# PR5007.net
KiCad netlist of a schematic drawn in EAGLE
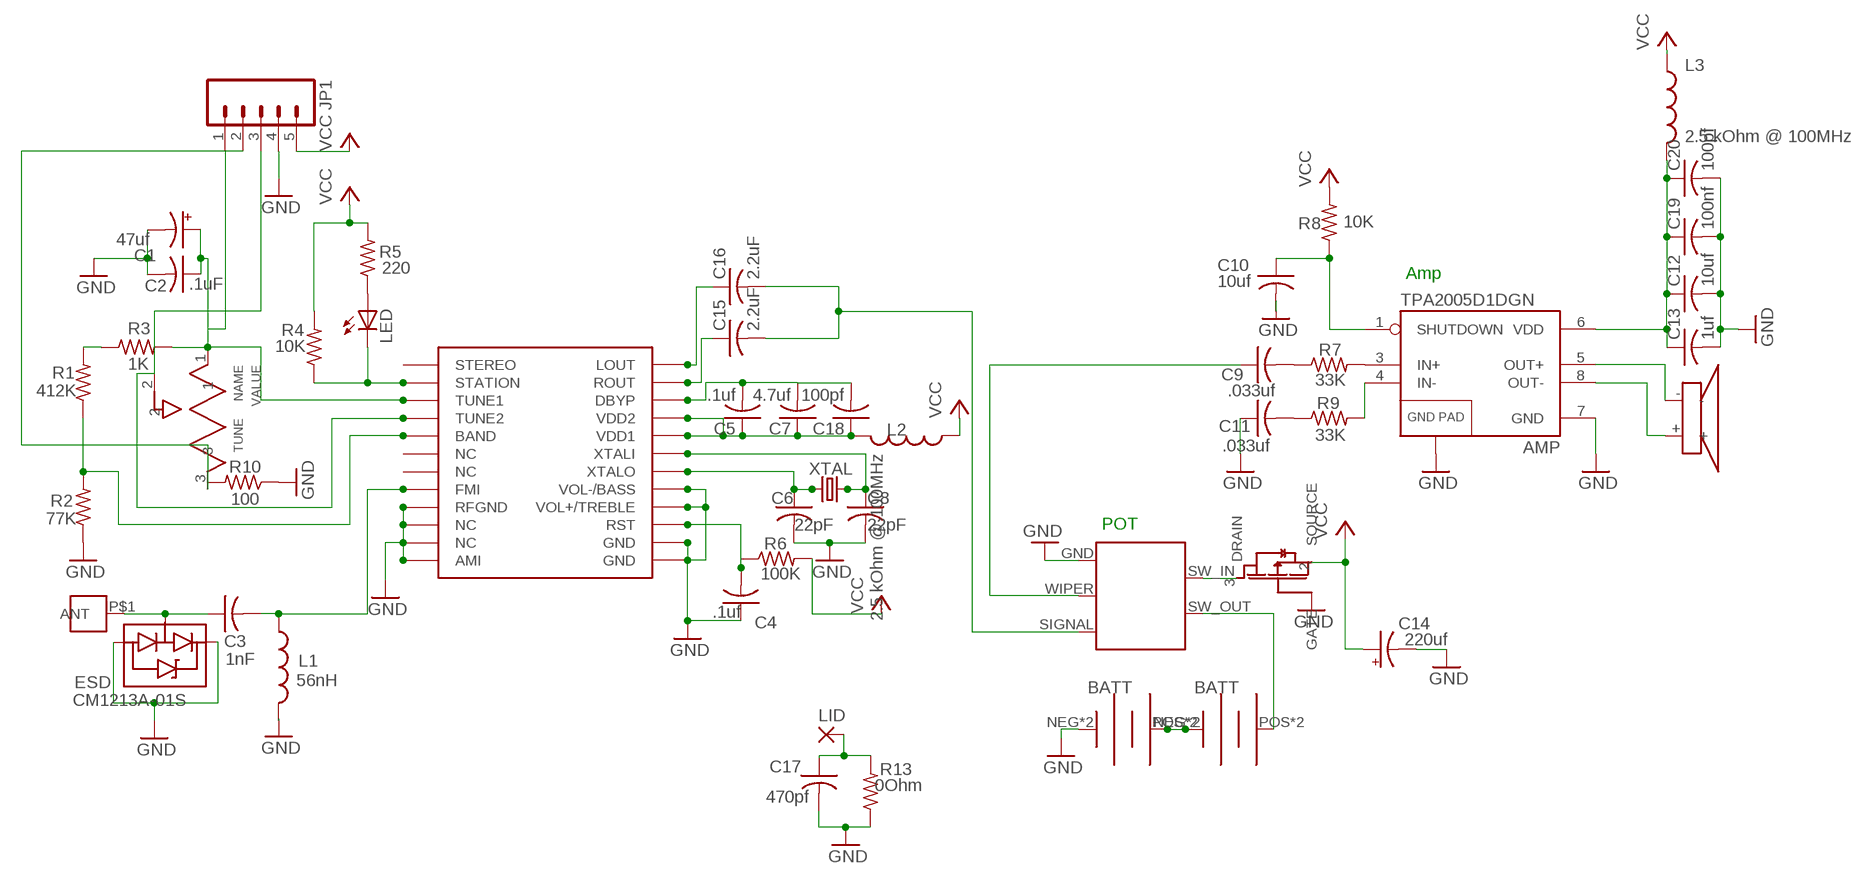
[diagram p0: schematic, sheet 1]

(export (version "E")
  (design (tool "Eeschema 10.0.6"))
  (components
    (comp (ref "AMP")
      (value "TPA2005D1DGN")
      (footprint "eagle-import:POWER-SOP8")
      (libsource (lib "eagle-import") (part "TPA2005D1DGN"))
    )
    (comp (ref "ANT")
      (value "M3_SCREW_POST")
      (footprint "eagle-import:M3_SCREW_POST")
      (libsource (lib "eagle-import") (part "M3_SCREW_POST"))
    )
    (comp (ref "C1")
      (value "47uf")
      (footprint "eagle-import:E2-5")
      (libsource (lib "eagle-import") (part "CPOL-USE2-5"))
    )
    (comp (ref "C2")
      (value ".1uF")
      (footprint "eagle-import:C0603")
      (libsource (lib "eagle-import") (part "C-USC0603"))
    )
    (comp (ref "C3")
      (value "1nF")
      (footprint "eagle-import:C0603")
      (libsource (lib "eagle-import") (part "C-USC0603"))
    )
    (comp (ref "C4")
      (value ".1uf")
      (footprint "eagle-import:C0603")
      (libsource (lib "eagle-import") (part "C-USC0603"))
    )
    (comp (ref "C5")
      (value ".1uf")
      (footprint "eagle-import:C0603")
      (libsource (lib "eagle-import") (part "C-USC0603"))
    )
    (comp (ref "C6")
      (value "22pF")
      (footprint "eagle-import:C0603")
      (libsource (lib "eagle-import") (part "C-USC0603"))
    )
    (comp (ref "C7")
      (value "4.7uf")
      (footprint "eagle-import:C0603")
      (libsource (lib "eagle-import") (part "C-USC0603"))
    )
    (comp (ref "C8")
      (value "22pF")
      (footprint "eagle-import:C0603")
      (libsource (lib "eagle-import") (part "C-USC0603"))
    )
    (comp (ref "C9")
      (value ".033uf")
      (footprint "eagle-import:C0603")
      (libsource (lib "eagle-import") (part "C-USC0603"))
    )
    (comp (ref "C10")
      (value "10uf")
      (footprint "eagle-import:C0603")
      (libsource (lib "eagle-import") (part "C-USC0603"))
    )
    (comp (ref "C11")
      (value ".033uf")
      (footprint "eagle-import:C0603")
      (libsource (lib "eagle-import") (part "C-USC0603"))
    )
    (comp (ref "C12")
      (value "10uf")
      (footprint "eagle-import:C0603")
      (libsource (lib "eagle-import") (part "C-USC0603"))
    )
    (comp (ref "C13")
      (value "1uf")
      (footprint "eagle-import:C0603")
      (libsource (lib "eagle-import") (part "C-USC0603"))
    )
    (comp (ref "C14")
      (value "220uf")
      (footprint "eagle-import:E2-5")
      (libsource (lib "eagle-import") (part "CPOL-USE2-5"))
    )
    (comp (ref "C15")
      (value "2.2uF")
      (footprint "eagle-import:C0603")
      (libsource (lib "eagle-import") (part "C-USC0603"))
    )
    (comp (ref "C16")
      (value "2.2uF")
      (footprint "eagle-import:C0603")
      (libsource (lib "eagle-import") (part "C-USC0603"))
    )
    (comp (ref "C17")
      (value "470pf")
      (footprint "eagle-import:C0805")
      (libsource (lib "eagle-import") (part "C-USC0805"))
    )
    (comp (ref "C18")
      (value "100pf")
      (footprint "eagle-import:C0603")
      (libsource (lib "eagle-import") (part "C-USC0603"))
    )
    (comp (ref "C19")
      (value "100nf")
      (footprint "eagle-import:C0603")
      (libsource (lib "eagle-import") (part "C-USC0603"))
    )
    (comp (ref "C20")
      (value "100pf")
      (footprint "eagle-import:C0603")
      (libsource (lib "eagle-import") (part "C-USC0603"))
    )
    (comp (ref "ESD")
      (value "CM1213A-01S")
      (footprint "eagle-import:SOT23-3")
      (libsource (lib "eagle-import") (part "CM1213A-01S"))
    )
    (comp (ref "FET")
      (value "SI2333DDS")
      (footprint "eagle-import:SI2333DDS")
      (libsource (lib "eagle-import") (part "SI2333DDS"))
    )
    (comp (ref "JP1")
      (value "M05LOCK")
      (footprint "eagle-import:1X05_LOCK")
      (libsource (lib "eagle-import") (part "M05LOCK"))
    )
    (comp (ref "L1")
      (value "56nH")
      (footprint "eagle-import:0603")
      (libsource (lib "eagle-import") (part "INDUCTOR0603"))
    )
    (comp (ref "L2")
      (value "2.5 kOhm @ 100MHz")
      (footprint "eagle-import:0603")
      (libsource (lib "eagle-import") (part "INDUCTOR0603"))
    )
    (comp (ref "L3")
      (value "2.5 kOhm @ 100MHz")
      (footprint "eagle-import:0603")
      (libsource (lib "eagle-import") (part "INDUCTOR0603"))
    )
    (comp (ref "LED")
      (value "LEDCHIPLED_0805")
      (footprint "eagle-import:CHIPLED_0805")
      (libsource (lib "eagle-import") (part "LEDCHIPLED_0805"))
    )
    (comp (ref "LID")
      (value "2,54/1,0")
      (footprint "eagle-import:2,54_1,0")
      (libsource (lib "eagle-import") (part "2,54/1,0"))
    )
    (comp (ref "R1")
      (value "412K")
      (footprint "eagle-import:R0603")
      (libsource (lib "eagle-import") (part "R-US_R0603"))
    )
    (comp (ref "R2")
      (value "77K")
      (footprint "eagle-import:R0603")
      (libsource (lib "eagle-import") (part "R-US_R0603"))
    )
    (comp (ref "R3")
      (value "1K")
      (footprint "eagle-import:R0603")
      (libsource (lib "eagle-import") (part "R-US_R0603"))
    )
    (comp (ref "R4")
      (value "10K")
      (footprint "eagle-import:R0603")
      (libsource (lib "eagle-import") (part "R-US_R0603"))
    )
    (comp (ref "R5")
      (value "220")
      (footprint "eagle-import:R0603")
      (libsource (lib "eagle-import") (part "R-US_R0603"))
    )
    (comp (ref "R6")
      (value "100K")
      (footprint "eagle-import:R0603")
      (libsource (lib "eagle-import") (part "R-US_R0603"))
    )
    (comp (ref "R7")
      (value "33K")
      (footprint "eagle-import:R0603")
      (libsource (lib "eagle-import") (part "R-US_R0603"))
    )
    (comp (ref "R8")
      (value "10K")
      (footprint "eagle-import:R0603")
      (libsource (lib "eagle-import") (part "R-US_R0603"))
    )
    (comp (ref "R9")
      (value "33K")
      (footprint "eagle-import:R0603")
      (libsource (lib "eagle-import") (part "R-US_R0603"))
    )
    (comp (ref "R10")
      (value "100")
      (footprint "eagle-import:R0603")
      (libsource (lib "eagle-import") (part "R-US_R0603"))
    )
    (comp (ref "R13")
      (value "0Ohm")
      (footprint "eagle-import:R0603")
      (libsource (lib "eagle-import") (part "R-US_R0603"))
    )
    (comp (ref "TUNE")
      (value "TUNE")
      (footprint "eagle-import:64XR_BOURNS_TRIMPOT")
      (libsource (lib "eagle-import") (part "64XR_BOURNS_TRIMPOT"))
    )
    (comp (ref "U$1")
      (value "BK-92_MPD_AA_BATT_CLIP")
      (footprint "eagle-import:BK-92_MPD_AA_BATT_CLIP")
      (libsource (lib "eagle-import") (part "BK-92_MPD_AA_BATT_CLIP"))
    )
    (comp (ref "U$2")
      (value "BK-92_MPD_AA_BATT_CLIP")
      (footprint "eagle-import:BK-92_MPD_AA_BATT_CLIP")
      (libsource (lib "eagle-import") (part "BK-92_MPD_AA_BATT_CLIP"))
    )
    (comp (ref "U$3")
      (value "CE32A_DAYTON_SPKR")
      (footprint "eagle-import:CE32A_DAYTON_SPKR")
      (libsource (lib "eagle-import") (part "CE32A_DAYTON_SPKR"))
    )
    (comp (ref "U$4")
      (value "SI4831_FM_IC")
      (footprint "eagle-import:SI4831_FM_IC")
      (libsource (lib "eagle-import") (part "SI4831_FM_IC"))
    )
    (comp (ref "U$5")
      (value "RV170SF_TAIWANA_POT_SW")
      (footprint "eagle-import:RV170SF_TAIWANA_POT_SW")
      (libsource (lib "eagle-import") (part "RV170SF_TAIWANA_POT_SW"))
    )
    (comp (ref "XTAL")
      (value "CRYSTAL32-SMD")
      (footprint "eagle-import:CRYSTAL-32KHZ-SMD")
      (libsource (lib "eagle-import") (part "CRYSTAL32-SMD"))
    )
  )
  (nets
    (net (code "1") (name "GND") (class "Default")
      (node (ref "AMP") (pin "7") (pinfunction "GND_7") (pintype "power_in"))
      (node (ref "AMP") (pin "9") (pinfunction "GND_9") (pintype "power_in"))
      (node (ref "C1") (pin "-") (pinfunction "-_-") (pintype "passive"))
      (node (ref "C10") (pin "2") (pinfunction "2_2") (pintype "passive"))
      (node (ref "C11") (pin "1") (pinfunction "1_1") (pintype "passive"))
      (node (ref "C12") (pin "2") (pinfunction "2_2") (pintype "passive"))
      (node (ref "C13") (pin "2") (pinfunction "2_2") (pintype "passive"))
      (node (ref "C14") (pin "-") (pinfunction "-_-") (pintype "passive"))
      (node (ref "C17") (pin "2") (pinfunction "2_2") (pintype "passive"))
      (node (ref "C19") (pin "2") (pinfunction "2_2") (pintype "passive"))
      (node (ref "C2") (pin "2") (pinfunction "2_2") (pintype "passive"))
      (node (ref "C20") (pin "2") (pinfunction "2_2") (pintype "passive"))
      (node (ref "C4") (pin "1") (pinfunction "1_1") (pintype "passive"))
      (node (ref "C6") (pin "2") (pinfunction "2_2") (pintype "passive"))
      (node (ref "C8") (pin "2") (pinfunction "2_2") (pintype "passive"))
      (node (ref "ESD") (pin "2") (pinfunction "VP_2") (pintype "passive"))
      (node (ref "ESD") (pin "3") (pinfunction "VN_3") (pintype "passive"))
      (node (ref "FET") (pin "1") (pinfunction "GATE_1") (pintype "bidirectional"))
      (node (ref "JP1") (pin "4") (pinfunction "4_4") (pintype "passive"))
      (node (ref "L1") (pin "2") (pinfunction "2_2") (pintype "passive"))
      (node (ref "R10") (pin "1") (pinfunction "1_1") (pintype "passive"))
      (node (ref "R13") (pin "1") (pinfunction "1_1") (pintype "passive"))
      (node (ref "R2") (pin "1") (pinfunction "1_1") (pintype "passive"))
      (node (ref "U$2") (pin "NEG") (pinfunction "NEG_NEG") (pintype "bidirectional"))
      (node (ref "U$2") (pin "NEG@2") (pinfunction "NEG_NEG@2") (pintype "bidirectional"))
      (node (ref "U$4") (pin "AMI") (pinfunction "AMI_AMI") (pintype "bidirectional"))
      (node (ref "U$4") (pin "GND") (pinfunction "GND_GND") (pintype "bidirectional"))
      (node (ref "U$4") (pin "GND@2") (pinfunction "GND_GND@2") (pintype "bidirectional"))
      (node (ref "U$4") (pin "NC@3") (pinfunction "NC_NC@3") (pintype "bidirectional"))
      (node (ref "U$4") (pin "NC@4") (pinfunction "NC_NC@4") (pintype "bidirectional"))
      (node (ref "U$4") (pin "RFGND") (pinfunction "RFGND_RFGND") (pintype "bidirectional"))
      (node (ref "U$4") (pin "VOL+/TREBLE") (pinfunction "VOL+/TREBLE_VOL+/TREBLE") (pintype "bidirectional"))
      (node (ref "U$4") (pin "VOL-/BASS") (pinfunction "VOL-/BASS_VOL-/BASS") (pintype "bidirectional"))
      (node (ref "U$5") (pin "GND") (pinfunction "GND_GND") (pintype "bidirectional"))
    )
    (net (code "2") (name "Net-(AMP-IN+)") (class "Default")
      (node (ref "AMP") (pin "3") (pinfunction "IN+_3") (pintype "bidirectional"))
      (node (ref "R7") (pin "2") (pinfunction "2_2") (pintype "passive"))
    )
    (net (code "3") (name "Net-(AMP-IN-)") (class "Default")
      (node (ref "AMP") (pin "4") (pinfunction "IN-_4") (pintype "bidirectional"))
      (node (ref "R9") (pin "2") (pinfunction "2_2") (pintype "passive"))
    )
    (net (code "4") (name "Net-(AMP-OUT+)") (class "Default")
      (node (ref "AMP") (pin "5") (pinfunction "OUT+_5") (pintype "bidirectional"))
      (node (ref "U$3") (pin "-") (pinfunction "-_-") (pintype "bidirectional"))
    )
    (net (code "5") (name "Net-(AMP-OUT-)") (class "Default")
      (node (ref "AMP") (pin "8") (pinfunction "OUT-_8") (pintype "bidirectional"))
      (node (ref "U$3") (pin "+") (pinfunction "+_+") (pintype "bidirectional"))
    )
    (net (code "6") (name "Net-(AMP-SHUTDOWN)") (class "Default")
      (node (ref "AMP") (pin "1") (pinfunction "SHUTDOWN_1") (pintype "input"))
      (node (ref "C10") (pin "1") (pinfunction "1_1") (pintype "passive"))
      (node (ref "R8") (pin "1") (pinfunction "1_1") (pintype "passive"))
    )
    (net (code "7") (name "Net-(AMP-VDD)") (class "Default")
      (node (ref "AMP") (pin "6") (pinfunction "VDD_6") (pintype "power_in"))
      (node (ref "C12") (pin "1") (pinfunction "1_1") (pintype "passive"))
      (node (ref "C13") (pin "1") (pinfunction "1_1") (pintype "passive"))
      (node (ref "C19") (pin "1") (pinfunction "1_1") (pintype "passive"))
      (node (ref "C20") (pin "1") (pinfunction "1_1") (pintype "passive"))
      (node (ref "L3") (pin "2") (pinfunction "2_2") (pintype "passive"))
    )
    (net (code "8") (name "Net-(ANT-ANT)") (class "Default")
      (node (ref "ANT") (pin "P$1") (pinfunction "ANT_P$1") (pintype "bidirectional"))
      (node (ref "C3") (pin "1") (pinfunction "1_1") (pintype "passive"))
      (node (ref "ESD") (pin "1") (pinfunction "CH_1") (pintype "passive"))
    )
    (net (code "9") (name "Net-(C1-Pad+)") (class "Default")
      (node (ref "C1") (pin "+") (pinfunction "+_+") (pintype "passive"))
      (node (ref "C2") (pin "1") (pinfunction "1_1") (pintype "passive"))
      (node (ref "JP1") (pin "1") (pinfunction "1_1") (pintype "passive"))
      (node (ref "R3") (pin "2") (pinfunction "2_2") (pintype "passive"))
      (node (ref "TUNE") (pin "1") (pinfunction "1_1") (pintype "bidirectional"))
      (node (ref "U$4") (pin "TUNE1") (pinfunction "TUNE1_TUNE1") (pintype "bidirectional"))
    )
    (net (code "10") (name "Net-(C3-Pad2)") (class "Default")
      (node (ref "C3") (pin "2") (pinfunction "2_2") (pintype "passive"))
      (node (ref "L1") (pin "1") (pinfunction "1_1") (pintype "passive"))
      (node (ref "U$4") (pin "FMI") (pinfunction "FMI_FMI") (pintype "bidirectional"))
    )
    (net (code "11") (name "Net-(C4-Pad2)") (class "Default")
      (node (ref "C4") (pin "2") (pinfunction "2_2") (pintype "passive"))
      (node (ref "R6") (pin "1") (pinfunction "1_1") (pintype "passive"))
      (node (ref "U$4") (pin "RST") (pinfunction "RST_RST") (pintype "bidirectional"))
    )
    (net (code "12") (name "Net-(C9-Pad1)") (class "Default")
      (node (ref "C9") (pin "1") (pinfunction "1_1") (pintype "passive"))
      (node (ref "U$5") (pin "WIPER") (pinfunction "WIPER_WIPER") (pintype "bidirectional"))
    )
    (net (code "13") (name "Net-(C9-Pad2)") (class "Default")
      (node (ref "C9") (pin "2") (pinfunction "2_2") (pintype "passive"))
      (node (ref "R7") (pin "1") (pinfunction "1_1") (pintype "passive"))
    )
    (net (code "14") (name "Net-(C11-Pad2)") (class "Default")
      (node (ref "C11") (pin "2") (pinfunction "2_2") (pintype "passive"))
      (node (ref "R9") (pin "1") (pinfunction "1_1") (pintype "passive"))
    )
    (net (code "15") (name "Net-(C15-Pad1)") (class "Default")
      (node (ref "C15") (pin "1") (pinfunction "1_1") (pintype "passive"))
      (node (ref "U$4") (pin "ROUT") (pinfunction "ROUT_ROUT") (pintype "bidirectional"))
    )
    (net (code "16") (name "Net-(C15-Pad2)") (class "Default")
      (node (ref "C15") (pin "2") (pinfunction "2_2") (pintype "passive"))
      (node (ref "C16") (pin "2") (pinfunction "2_2") (pintype "passive"))
      (node (ref "U$5") (pin "SIGNAL") (pinfunction "SIGNAL_SIGNAL") (pintype "bidirectional"))
    )
    (net (code "17") (name "Net-(C16-Pad1)") (class "Default")
      (node (ref "C16") (pin "1") (pinfunction "1_1") (pintype "passive"))
      (node (ref "U$4") (pin "LOUT") (pinfunction "LOUT_LOUT") (pintype "bidirectional"))
    )
    (net (code "18") (name "Net-(C18-Pad1)") (class "Default")
      (node (ref "C18") (pin "1") (pinfunction "1_1") (pintype "passive"))
      (node (ref "C5") (pin "1") (pinfunction "1_1") (pintype "passive"))
      (node (ref "C7") (pin "1") (pinfunction "1_1") (pintype "passive"))
      (node (ref "L2") (pin "2") (pinfunction "2_2") (pintype "passive"))
      (node (ref "U$4") (pin "VDD1") (pinfunction "VDD1_VDD1") (pintype "bidirectional"))
      (node (ref "U$4") (pin "VDD2") (pinfunction "VDD2_VDD2") (pintype "bidirectional"))
    )
    (net (code "19") (name "Net-(C18-Pad2)") (class "Default")
      (node (ref "C18") (pin "2") (pinfunction "2_2") (pintype "passive"))
      (node (ref "C5") (pin "2") (pinfunction "2_2") (pintype "passive"))
      (node (ref "C7") (pin "2") (pinfunction "2_2") (pintype "passive"))
      (node (ref "U$4") (pin "DBYP") (pinfunction "DBYP_DBYP") (pintype "bidirectional"))
    )
    (net (code "20") (name "Net-(FET-DRAIN)") (class "Default")
      (node (ref "FET") (pin "3") (pinfunction "DRAIN_3") (pintype "bidirectional"))
      (node (ref "U$5") (pin "SW_IN") (pinfunction "SW_IN_SW_IN") (pintype "bidirectional"))
    )
    (net (code "21") (name "Net-(JP1-Pad2)") (class "Default")
      (node (ref "JP1") (pin "2") (pinfunction "2_2") (pintype "passive"))
      (node (ref "R10") (pin "2") (pinfunction "2_2") (pintype "passive"))
      (node (ref "TUNE") (pin "3") (pinfunction "3_3") (pintype "bidirectional"))
    )
    (net (code "22") (name "Net-(JP1-Pad3)") (class "Default")
      (node (ref "JP1") (pin "3") (pinfunction "3_3") (pintype "passive"))
      (node (ref "TUNE") (pin "2") (pinfunction "2_2") (pintype "bidirectional"))
      (node (ref "U$4") (pin "TUNE2") (pinfunction "TUNE2_TUNE2") (pintype "bidirectional"))
    )
    (net (code "23") (name "Net-(LED-PadA)") (class "Default")
      (node (ref "LED") (pin "A") (pinfunction "A_A") (pintype "passive"))
      (node (ref "R5") (pin "1") (pinfunction "1_1") (pintype "passive"))
    )
    (net (code "24") (name "Net-(LED-PadC)") (class "Default")
      (node (ref "LED") (pin "C") (pinfunction "C_C") (pintype "passive"))
      (node (ref "R4") (pin "1") (pinfunction "1_1") (pintype "passive"))
      (node (ref "U$4") (pin "STATION") (pinfunction "STATION_STATION") (pintype "bidirectional"))
    )
    (net (code "25") (name "Net-(LID-P)") (class "Default")
      (node (ref "C17") (pin "1") (pinfunction "1_1") (pintype "passive"))
      (node (ref "LID") (pin "1") (pinfunction "P_1") (pintype "passive"))
      (node (ref "R13") (pin "2") (pinfunction "2_2") (pintype "passive"))
    )
    (net (code "26") (name "Net-(R1-Pad1)") (class "Default")
      (node (ref "R1") (pin "1") (pinfunction "1_1") (pintype "passive"))
      (node (ref "R2") (pin "2") (pinfunction "2_2") (pintype "passive"))
      (node (ref "U$4") (pin "BAND") (pinfunction "BAND_BAND") (pintype "bidirectional"))
    )
    (net (code "27") (name "Net-(R1-Pad2)") (class "Default")
      (node (ref "R1") (pin "2") (pinfunction "2_2") (pintype "passive"))
      (node (ref "R3") (pin "1") (pinfunction "1_1") (pintype "passive"))
    )
    (net (code "28") (name "Net-(U$1-NEG-PadNEG@2)") (class "Default")
      (node (ref "U$1") (pin "NEG") (pinfunction "NEG_NEG") (pintype "bidirectional"))
      (node (ref "U$1") (pin "NEG@2") (pinfunction "NEG_NEG@2") (pintype "bidirectional"))
      (node (ref "U$2") (pin "POS") (pinfunction "POS_POS") (pintype "bidirectional"))
      (node (ref "U$2") (pin "POS@2") (pinfunction "POS_POS@2") (pintype "bidirectional"))
    )
    (net (code "29") (name "Net-(U$1-POS-PadPOS@2)") (class "Default")
      (node (ref "U$1") (pin "POS") (pinfunction "POS_POS") (pintype "bidirectional"))
      (node (ref "U$1") (pin "POS@2") (pinfunction "POS_POS@2") (pintype "bidirectional"))
      (node (ref "U$5") (pin "SW_OUT") (pinfunction "SW_OUT_SW_OUT") (pintype "bidirectional"))
    )
    (net (code "30") (name "Net-(XTAL-1)") (class "Default")
      (node (ref "C8") (pin "1") (pinfunction "1_1") (pintype "passive"))
      (node (ref "U$4") (pin "XTALI") (pinfunction "XTALI_XTALI") (pintype "bidirectional"))
      (node (ref "XTAL") (pin "X1") (pinfunction "1_X1") (pintype "passive"))
    )
    (net (code "31") (name "Net-(XTAL-2)") (class "Default")
      (node (ref "C6") (pin "1") (pinfunction "1_1") (pintype "passive"))
      (node (ref "U$4") (pin "XTALO") (pinfunction "XTALO_XTALO") (pintype "bidirectional"))
      (node (ref "XTAL") (pin "X2") (pinfunction "2_X2") (pintype "passive"))
    )
    (net (code "32") (name "VCC") (class "Default")
      (node (ref "C14") (pin "+") (pinfunction "+_+") (pintype "passive"))
      (node (ref "FET") (pin "2") (pinfunction "SOURCE_2") (pintype "bidirectional"))
      (node (ref "JP1") (pin "5") (pinfunction "5_5") (pintype "passive"))
      (node (ref "L2") (pin "1") (pinfunction "1_1") (pintype "passive"))
      (node (ref "L3") (pin "1") (pinfunction "1_1") (pintype "passive"))
      (node (ref "R4") (pin "2") (pinfunction "2_2") (pintype "passive"))
      (node (ref "R5") (pin "2") (pinfunction "2_2") (pintype "passive"))
      (node (ref "R6") (pin "2") (pinfunction "2_2") (pintype "passive"))
      (node (ref "R8") (pin "2") (pinfunction "2_2") (pintype "passive"))
    )
    (net (code "33") (name "unconnected-(U$4-NC-PadNC@2)") (class "Default")
      (node (ref "U$4") (pin "NC@2") (pinfunction "NC_NC@2") (pintype "bidirectional"))
    )
    (net (code "34") (name "unconnected-(U$4-PadNC)") (class "Default")
      (node (ref "U$4") (pin "NC") (pinfunction "NC_NC") (pintype "bidirectional"))
    )
    (net (code "35") (name "unconnected-(U$4-PadSTEREO)") (class "Default")
      (node (ref "U$4") (pin "STEREO") (pinfunction "STEREO_STEREO") (pintype "bidirectional"))
    )
  )
)
